# untitled.net
KiCad netlist of a schematic drawn in EAGLE
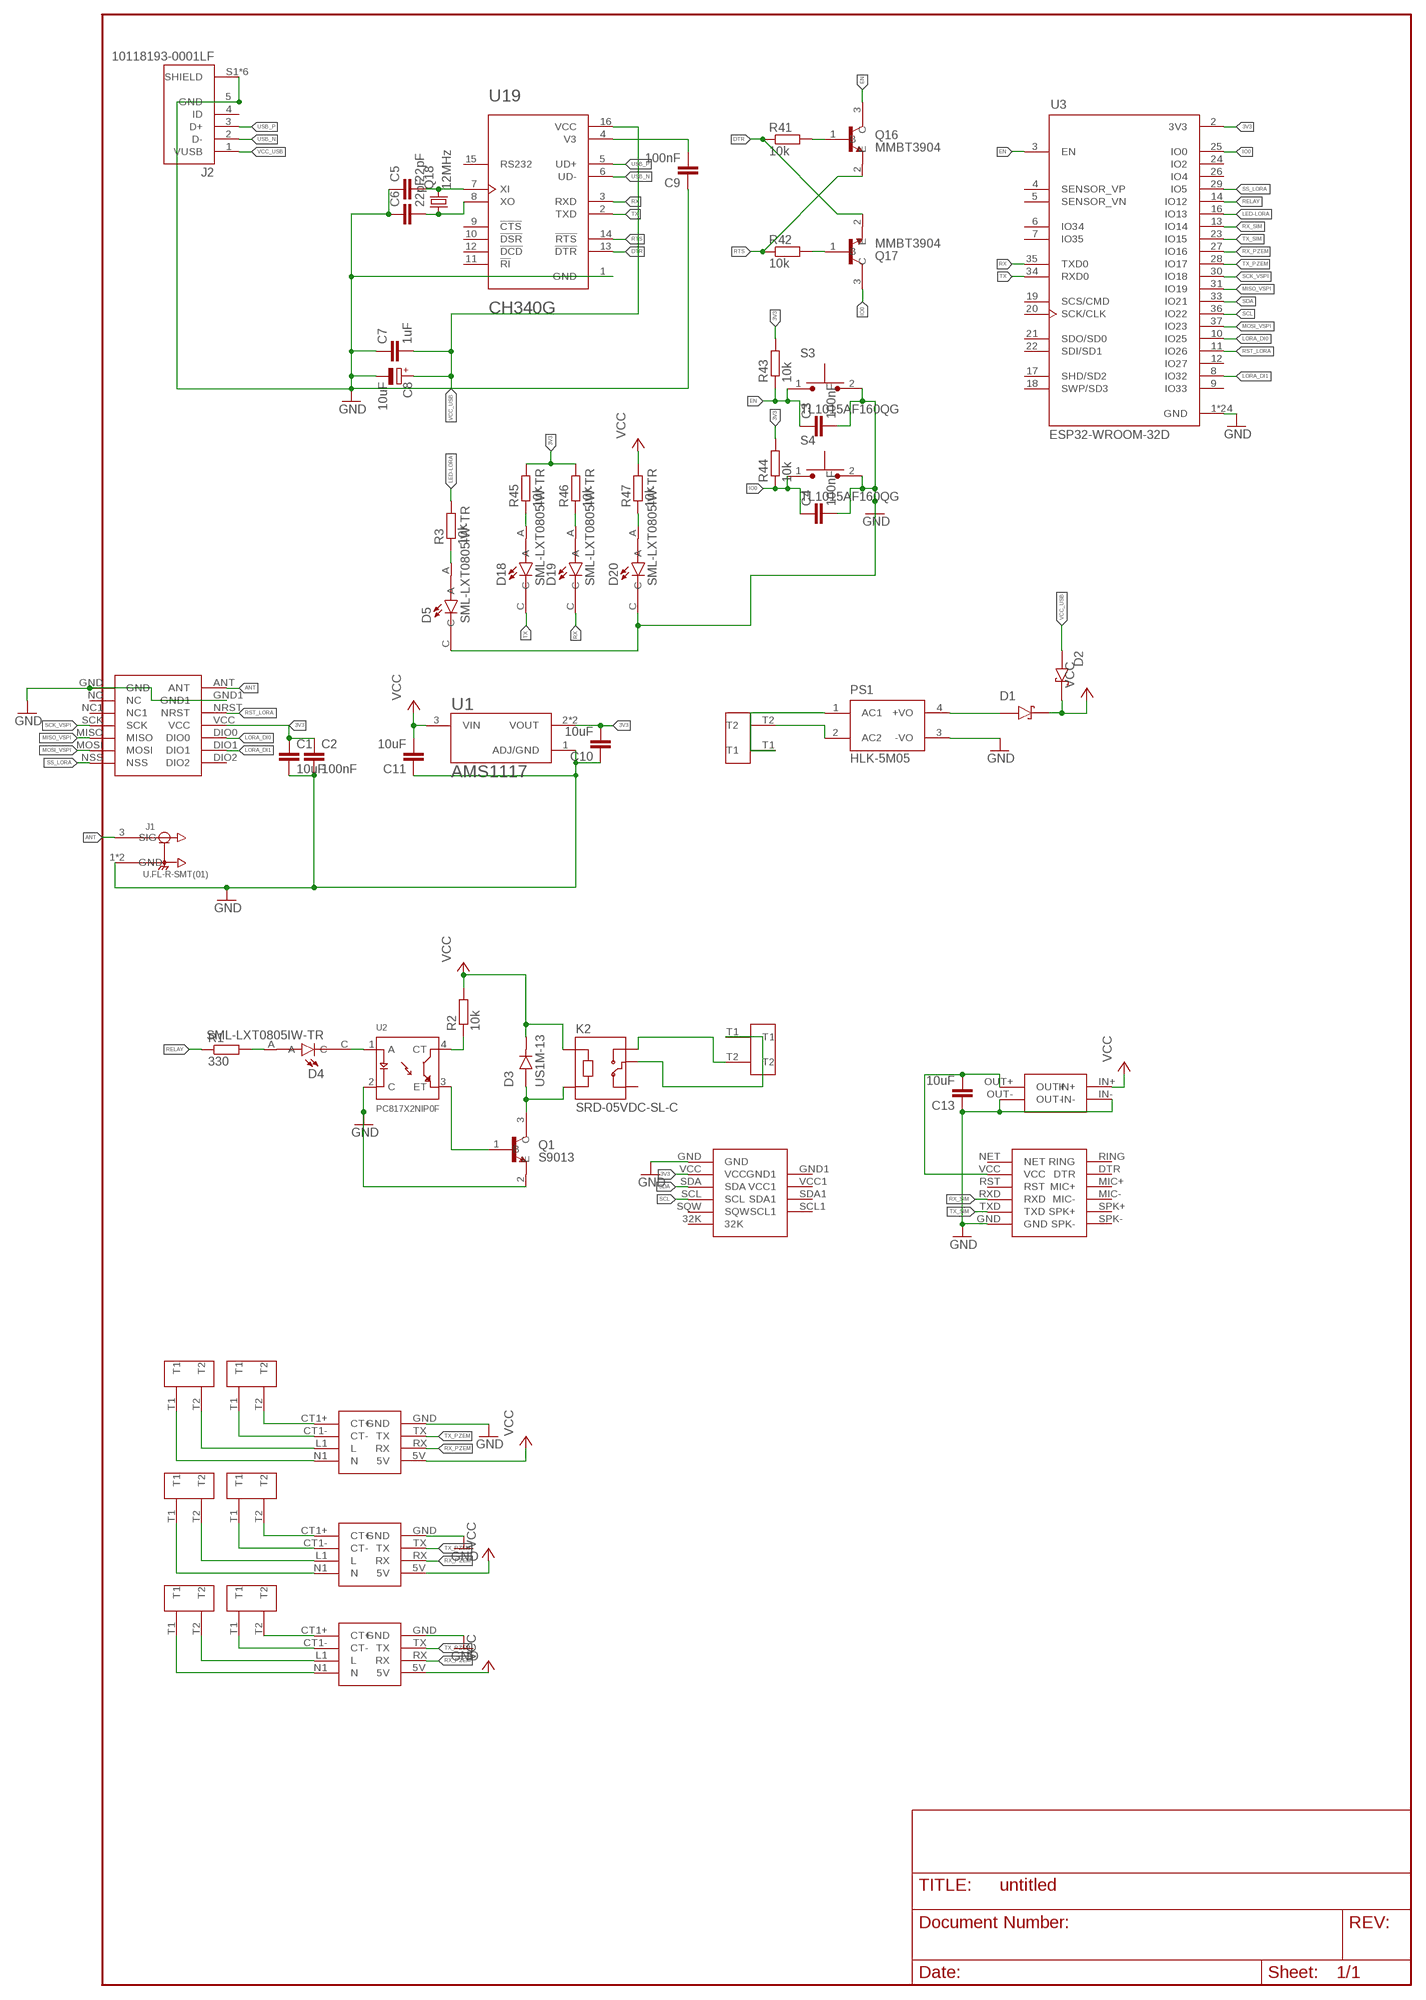
[diagram p0: schematic, sheet 1]

(export (version "E")
  (design (tool "Eeschema 10.0.6"))
  (components
    (comp (ref "C1")
      (value "10uF")
      (footprint "eagle-import:C0805K")
      (libsource (lib "eagle-import") (part "C-EUC0805K"))
    )
    (comp (ref "C2")
      (value "100nF")
      (footprint "eagle-import:C0805K")
      (libsource (lib "eagle-import") (part "C-EUC0805K"))
    )
    (comp (ref "C3")
      (value "100nF")
      (footprint "eagle-import:C0805K")
      (libsource (lib "eagle-import") (part "C-EUC0805K"))
    )
    (comp (ref "C4")
      (value "100nF")
      (footprint "eagle-import:C0805K")
      (libsource (lib "eagle-import") (part "C-EUC0805K"))
    )
    (comp (ref "C5")
      (value "22pF")
      (footprint "eagle-import:C0805K")
      (libsource (lib "eagle-import") (part "C-EUC0805K"))
    )
    (comp (ref "C6")
      (value "22pF")
      (footprint "eagle-import:C0805K")
      (libsource (lib "eagle-import") (part "C-EUC0805K"))
    )
    (comp (ref "C7")
      (value "1uF")
      (footprint "eagle-import:C0805K")
      (libsource (lib "eagle-import") (part "C-EUC0805K"))
    )
    (comp (ref "C8")
      (value "10uF")
      (footprint "eagle-import:153CLV-0505")
      (libsource (lib "eagle-import") (part "CPOL-EU153CLV-0505"))
    )
    (comp (ref "C9")
      (value "100nF")
      (footprint "eagle-import:C0805K")
      (libsource (lib "eagle-import") (part "C-EUC0805K"))
    )
    (comp (ref "C10")
      (value "10uF")
      (footprint "eagle-import:C0805K")
      (libsource (lib "eagle-import") (part "C-EUC0805K"))
    )
    (comp (ref "C11")
      (value "10uF")
      (footprint "eagle-import:C0805K")
      (libsource (lib "eagle-import") (part "C-EUC0805K"))
    )
    (comp (ref "C13")
      (value "10uF")
      (footprint "eagle-import:C0805K")
      (libsource (lib "eagle-import") (part "C-EUC0805K"))
    )
    (comp (ref "D1")
      (value "1N5819HW-7")
      (footprint "eagle-import:SOD3715X145N")
      (fields (field (name "MF") "Diodes Inc."))
      (libsource (lib "eagle-import") (part "1N5819HW-7"))
    )
    (comp (ref "D2")
      (value "1N5819HW-7")
      (footprint "eagle-import:SOD3715X145N")
      (fields (field (name "MF") "Diodes Inc."))
      (libsource (lib "eagle-import") (part "1N5819HW-7"))
    )
    (comp (ref "D3")
      (value "US1M-13")
      (footprint "eagle-import:DIOM5226X240N")
      (fields (field (name "MF") "Diodes Incorporated"))
      (libsource (lib "eagle-import") (part "US1M-13"))
    )
    (comp (ref "D4")
      (value "SML-LXT0805IW-TR")
      (footprint "eagle-import:LEDC2012X120N")
      (fields (field (name "MF") "Lumex Opto/Components"))
      (libsource (lib "eagle-import") (part "SML-LXT0805IW-TR"))
    )
    (comp (ref "D5")
      (value "SML-LXT0805IW-TR")
      (footprint "eagle-import:LEDC2012X120N")
      (fields (field (name "MF") "Lumex Opto/Components"))
      (libsource (lib "eagle-import") (part "SML-LXT0805IW-TR"))
    )
    (comp (ref "D18")
      (value "SML-LXT0805IW-TR")
      (footprint "eagle-import:LEDC2012X120N")
      (fields (field (name "MF") "Lumex Opto/Components"))
      (libsource (lib "eagle-import") (part "SML-LXT0805IW-TR"))
    )
    (comp (ref "D19")
      (value "SML-LXT0805IW-TR")
      (footprint "eagle-import:LEDC2012X120N")
      (fields (field (name "MF") "Lumex Opto/Components"))
      (libsource (lib "eagle-import") (part "SML-LXT0805IW-TR"))
    )
    (comp (ref "D20")
      (value "SML-LXT0805IW-TR")
      (footprint "eagle-import:LEDC2012X120N")
      (fields (field (name "MF") "Lumex Opto/Components"))
      (libsource (lib "eagle-import") (part "SML-LXT0805IW-TR"))
    )
    (comp (ref "J1")
      (value "U.FL-R-SMT(01)")
      (footprint "eagle-import:HRS_U.FL-R-SMT(01)")
      (fields (field (name "MF") "Hirose"))
      (libsource (lib "eagle-import") (part "U.FL-R-SMT(01)"))
    )
    (comp (ref "J2")
      (value "10118193-0001LF")
      (footprint "eagle-import:FCI_10118193-0001LF")
      (fields (field (name "MF") "FCI"))
      (libsource (lib "eagle-import") (part "10118193-0001LF"))
    )
    (comp (ref "K2")
      (value "SRD-05VDC-SL-C")
      (footprint "eagle-import:RELAY_SRD-05VDC-SL-C")
      (fields (field (name "MF") "Songle Relay"))
      (libsource (lib "eagle-import") (part "SRD-05VDC-SL-C"))
    )
    (comp (ref "LORA-NICERF-V1")
      (value "LORA-NICERF-V2")
      (footprint "eagle-import:LORA-NICERF-V2")
      (libsource (lib "eagle-import") (part "LORA-NICERF-V2"))
    )
    (comp (ref "MINI1")
      (value "MINI360")
      (footprint "eagle-import:MINI360")
      (libsource (lib "eagle-import") (part "MINI360"))
    )
    (comp (ref "PS1")
      (value "HLK-5M05")
      (footprint "eagle-import:CONV_HLK-5M05")
      (fields (field (name "MF") "Hi-link"))
      (libsource (lib "eagle-import") (part "HLK-5M05"))
    )
    (comp (ref "PZEM004T1")
      (value "PZEM004T")
      (footprint "eagle-import:PZEM004T")
      (libsource (lib "eagle-import") (part "PZEM004T"))
    )
    (comp (ref "PZEM004T2")
      (value "PZEM004T")
      (footprint "eagle-import:PZEM004T")
      (libsource (lib "eagle-import") (part "PZEM004T"))
    )
    (comp (ref "PZEM004T3")
      (value "PZEM004T")
      (footprint "eagle-import:PZEM004T")
      (libsource (lib "eagle-import") (part "PZEM004T"))
    )
    (comp (ref "Q1")
      (value "S9013")
      (footprint "eagle-import:SOT95P240X120-3N")
      (fields (field (name "MF") "JCET"))
      (libsource (lib "eagle-import") (part "S9013"))
    )
    (comp (ref "Q16")
      (value "MMBT3904")
      (footprint "eagle-import:SOT95P240X120-3N")
      (fields (field (name "MF") "ON Semiconductor"))
      (libsource (lib "eagle-import") (part "MMBT3904"))
    )
    (comp (ref "Q17")
      (value "MMBT3904")
      (footprint "eagle-import:SOT95P240X120-3N")
      (fields (field (name "MF") "ON Semiconductor"))
      (libsource (lib "eagle-import") (part "MMBT3904"))
    )
    (comp (ref "Q18")
      (value "12MHz")
      (footprint "eagle-import:SM49")
      (libsource (lib "eagle-import") (part "CRYSTALSM49"))
    )
    (comp (ref "R1")
      (value "330")
      (footprint "eagle-import:R0805")
      (libsource (lib "eagle-import") (part "R-EU_R0805"))
    )
    (comp (ref "R2")
      (value "10k")
      (footprint "eagle-import:R0805")
      (libsource (lib "eagle-import") (part "R-EU_R0805"))
    )
    (comp (ref "R3")
      (value "10k")
      (footprint "eagle-import:R0805")
      (libsource (lib "eagle-import") (part "R-EU_R0805"))
    )
    (comp (ref "R41")
      (value "10k")
      (footprint "eagle-import:R0805")
      (libsource (lib "eagle-import") (part "R-EU_R0805"))
    )
    (comp (ref "R42")
      (value "10k")
      (footprint "eagle-import:R0805")
      (libsource (lib "eagle-import") (part "R-EU_R0805"))
    )
    (comp (ref "R43")
      (value "10k")
      (footprint "eagle-import:R0805")
      (libsource (lib "eagle-import") (part "R-EU_R0805"))
    )
    (comp (ref "R44")
      (value "10k")
      (footprint "eagle-import:R0805")
      (libsource (lib "eagle-import") (part "R-EU_R0805"))
    )
    (comp (ref "R45")
      (value "10k")
      (footprint "eagle-import:R0805")
      (libsource (lib "eagle-import") (part "R-EU_R0805"))
    )
    (comp (ref "R46")
      (value "10k")
      (footprint "eagle-import:R0805")
      (libsource (lib "eagle-import") (part "R-EU_R0805"))
    )
    (comp (ref "R47")
      (value "10k")
      (footprint "eagle-import:R0805")
      (libsource (lib "eagle-import") (part "R-EU_R0805"))
    )
    (comp (ref "RTC1")
      (value "RTC3231")
      (footprint "eagle-import:RTC3231")
      (libsource (lib "eagle-import") (part "RTC3231"))
    )
    (comp (ref "S3")
      (value "TL1015AF160QG")
      (footprint "eagle-import:SW_TL1015AF160QG")
      (fields (field (name "MF") "E-Switch"))
      (libsource (lib "eagle-import") (part "TL1015AF160QG"))
    )
    (comp (ref "S4")
      (value "TL1015AF160QG")
      (footprint "eagle-import:SW_TL1015AF160QG")
      (fields (field (name "MF") "E-Switch"))
      (libsource (lib "eagle-import") (part "TL1015AF160QG"))
    )
    (comp (ref "SIM800L1")
      (value "SIM800L")
      (footprint "eagle-import:SIM800L")
      (libsource (lib "eagle-import") (part "SIM800L"))
    )
    (comp (ref "TB7.1")
      (value "TB7.62")
      (footprint "eagle-import:TB7.62")
      (libsource (lib "eagle-import") (part "TB7.62"))
    )
    (comp (ref "TB7.2")
      (value "TB7.62")
      (footprint "eagle-import:TB7.62")
      (libsource (lib "eagle-import") (part "TB7.62"))
    )
    (comp (ref "TB7.3")
      (value "TB7.62")
      (footprint "eagle-import:TB7.62")
      (libsource (lib "eagle-import") (part "TB7.62"))
    )
    (comp (ref "TB7.4")
      (value "TB7.62")
      (footprint "eagle-import:TB7.62")
      (libsource (lib "eagle-import") (part "TB7.62"))
    )
    (comp (ref "TB7.5")
      (value "TB7.62")
      (footprint "eagle-import:TB7.62")
      (libsource (lib "eagle-import") (part "TB7.62"))
    )
    (comp (ref "TB7.6")
      (value "TB7.62")
      (footprint "eagle-import:TB7.62")
      (libsource (lib "eagle-import") (part "TB7.62"))
    )
    (comp (ref "TB7.7")
      (value "TB7.62")
      (footprint "eagle-import:TB7.62")
      (libsource (lib "eagle-import") (part "TB7.62"))
    )
    (comp (ref "TB7.8")
      (value "TB7.62")
      (footprint "eagle-import:TB7.62")
      (libsource (lib "eagle-import") (part "TB7.62"))
    )
    (comp (ref "U1")
      (value "AMS1117")
      (footprint "eagle-import:SOT229P700X180-4N")
      (fields (field (name "MF") "Advanced Monolithic Systems"))
      (libsource (lib "eagle-import") (part "AMS1117"))
    )
    (comp (ref "U2")
      (value "PC817X2NIP0F")
      (footprint "eagle-import:SOT254P975X400-4N")
      (fields (field (name "MF") "Sharp Microelectronics"))
      (libsource (lib "eagle-import") (part "PC817X2NIP0F"))
    )
    (comp (ref "U3")
      (value "ESP32-WROOM-32D")
      (footprint "eagle-import:MODULE_ESP32-WROOM-32D")
      (fields (field (name "MF") "Espressif Systems"))
      (libsource (lib "eagle-import") (part "ESP32-WROOM-32D"))
    )
    (comp (ref "U19")
      (value "CH340G")
      (footprint "eagle-import:SOIC127P600X180-16N")
      (fields (field (name "MF") "WCH") (field (name "MP") "Ch340G"))
      (libsource (lib "eagle-import") (part "CH340G"))
    )
  )
  (nets
    (net (code "1") (name "3V3") (class "Default")
      (node (ref "C1") (pin "1") (pinfunction "1_1") (pintype "passive"))
      (node (ref "C10") (pin "2") (pinfunction "2_2") (pintype "passive"))
      (node (ref "C2") (pin "1") (pinfunction "1_1") (pintype "passive"))
      (node (ref "LORA-NICERF-V1") (pin "VCC") (pinfunction "VCC_VCC") (pintype "bidirectional"))
      (node (ref "R43") (pin "2") (pinfunction "2_2") (pintype "passive"))
      (node (ref "R44") (pin "2") (pinfunction "2_2") (pintype "passive"))
      (node (ref "R45") (pin "2") (pinfunction "2_2") (pintype "passive"))
      (node (ref "R46") (pin "2") (pinfunction "2_2") (pintype "passive"))
      (node (ref "RTC1") (pin "VCC") (pinfunction "VCC_VCC") (pintype "bidirectional"))
      (node (ref "U1") (pin "2") (pinfunction "VOUT_2") (pintype "output"))
      (node (ref "U1") (pin "4") (pinfunction "VOUT_4") (pintype "output"))
      (node (ref "U3") (pin "2") (pinfunction "3V3_2") (pintype "power_in"))
    )
    (net (code "2") (name "ANT") (class "Default")
      (node (ref "J1") (pin "3") (pinfunction "SIG_3") (pintype "passive"))
      (node (ref "LORA-NICERF-V1") (pin "ANT") (pinfunction "ANT_ANT") (pintype "bidirectional"))
    )
    (net (code "3") (name "DTR") (class "Default")
      (node (ref "Q17") (pin "2") (pinfunction "E_2") (pintype "passive"))
      (node (ref "R41") (pin "1") (pinfunction "1_1") (pintype "passive"))
      (node (ref "U19") (pin "13") (pinfunction "~{DTR}_13") (pintype "output"))
    )
    (net (code "4") (name "EN") (class "Default")
      (node (ref "C3") (pin "1") (pinfunction "1_1") (pintype "passive"))
      (node (ref "Q16") (pin "3") (pinfunction "C_3") (pintype "passive"))
      (node (ref "R43") (pin "1") (pinfunction "1_1") (pintype "passive"))
      (node (ref "S3") (pin "1") (pinfunction "1_1") (pintype "passive"))
      (node (ref "U3") (pin "3") (pinfunction "EN_3") (pintype "input"))
    )
    (net (code "5") (name "GND") (class "Default")
      (node (ref "C1") (pin "2") (pinfunction "2_2") (pintype "passive"))
      (node (ref "C10") (pin "1") (pinfunction "1_1") (pintype "passive"))
      (node (ref "C11") (pin "1") (pinfunction "1_1") (pintype "passive"))
      (node (ref "C13") (pin "1") (pinfunction "1_1") (pintype "passive"))
      (node (ref "C2") (pin "2") (pinfunction "2_2") (pintype "passive"))
      (node (ref "C3") (pin "2") (pinfunction "2_2") (pintype "passive"))
      (node (ref "C4") (pin "2") (pinfunction "2_2") (pintype "passive"))
      (node (ref "C5") (pin "1") (pinfunction "1_1") (pintype "passive"))
      (node (ref "C6") (pin "1") (pinfunction "1_1") (pintype "passive"))
      (node (ref "C7") (pin "1") (pinfunction "1_1") (pintype "passive"))
      (node (ref "C8") (pin "-") (pinfunction "-_-") (pintype "passive"))
      (node (ref "C9") (pin "1") (pinfunction "1_1") (pintype "passive"))
      (node (ref "D20") (pin "C") (pinfunction "C_C") (pintype "passive"))
      (node (ref "D5") (pin "C") (pinfunction "C_C") (pintype "passive"))
      (node (ref "J1") (pin "1") (pinfunction "GND_1") (pintype "passive"))
      (node (ref "J1") (pin "2") (pinfunction "GND_2") (pintype "passive"))
      (node (ref "J2") (pin "5") (pinfunction "GND_5") (pintype "passive"))
      (node (ref "J2") (pin "S1") (pinfunction "SHIELD_S1") (pintype "passive"))
      (node (ref "J2") (pin "S2") (pinfunction "SHIELD_S2") (pintype "passive"))
      (node (ref "J2") (pin "S3") (pinfunction "SHIELD_S3") (pintype "passive"))
      (node (ref "J2") (pin "S4") (pinfunction "SHIELD_S4") (pintype "passive"))
      (node (ref "J2") (pin "S5") (pinfunction "SHIELD_S5") (pintype "passive"))
      (node (ref "J2") (pin "S6") (pinfunction "SHIELD_S6") (pintype "passive"))
      (node (ref "LORA-NICERF-V1") (pin "GND") (pinfunction "GND_GND") (pintype "bidirectional"))
      (node (ref "LORA-NICERF-V1") (pin "GND1") (pinfunction "GND1_GND1") (pintype "bidirectional"))
      (node (ref "MINI1") (pin "IN-") (pinfunction "IN-_IN-") (pintype "bidirectional"))
      (node (ref "MINI1") (pin "OUT-") (pinfunction "OUT-_OUT-") (pintype "bidirectional"))
      (node (ref "PS1") (pin "3") (pinfunction "-VO_3") (pintype "output"))
      (node (ref "PZEM004T1") (pin "GND") (pinfunction "GND_GND") (pintype "bidirectional"))
      (node (ref "PZEM004T2") (pin "GND") (pinfunction "GND_GND") (pintype "bidirectional"))
      (node (ref "PZEM004T3") (pin "GND") (pinfunction "GND_GND") (pintype "bidirectional"))
      (node (ref "Q1") (pin "2") (pinfunction "E_2") (pintype "passive"))
      (node (ref "RTC1") (pin "GND") (pinfunction "GND_GND") (pintype "bidirectional"))
      (node (ref "S3") (pin "2") (pinfunction "2_2") (pintype "passive"))
      (node (ref "S4") (pin "2") (pinfunction "2_2") (pintype "passive"))
      (node (ref "SIM800L1") (pin "GND") (pinfunction "GND_GND") (pintype "bidirectional"))
      (node (ref "U1") (pin "1") (pinfunction "ADJ/GND_1") (pintype "power_in"))
      (node (ref "U19") (pin "1") (pinfunction "GND_1") (pintype "power_in"))
      (node (ref "U2") (pin "2") (pinfunction "C_2") (pintype "passive"))
      (node (ref "U3") (pin "1") (pinfunction "GND_1") (pintype "power_in"))
      (node (ref "U3") (pin "15") (pinfunction "GND_15") (pintype "power_in"))
      (node (ref "U3") (pin "38") (pinfunction "GND_38") (pintype "power_in"))
      (node (ref "U3") (pin "39_1") (pinfunction "GND_39_1") (pintype "power_in"))
      (node (ref "U3") (pin "39_10") (pinfunction "GND_39_10") (pintype "power_in"))
      (node (ref "U3") (pin "39_11") (pinfunction "GND_39_11") (pintype "power_in"))
      (node (ref "U3") (pin "39_12") (pinfunction "GND_39_12") (pintype "power_in"))
      (node (ref "U3") (pin "39_13") (pinfunction "GND_39_13") (pintype "power_in"))
      (node (ref "U3") (pin "39_14") (pinfunction "GND_39_14") (pintype "power_in"))
      (node (ref "U3") (pin "39_15") (pinfunction "GND_39_15") (pintype "power_in"))
      (node (ref "U3") (pin "39_16") (pinfunction "GND_39_16") (pintype "power_in"))
      (node (ref "U3") (pin "39_17") (pinfunction "GND_39_17") (pintype "power_in"))
      (node (ref "U3") (pin "39_18") (pinfunction "GND_39_18") (pintype "power_in"))
      (node (ref "U3") (pin "39_19") (pinfunction "GND_39_19") (pintype "power_in"))
      (node (ref "U3") (pin "39_2") (pinfunction "GND_39_2") (pintype "power_in"))
      (node (ref "U3") (pin "39_20") (pinfunction "GND_39_20") (pintype "power_in"))
      (node (ref "U3") (pin "39_21") (pinfunction "GND_39_21") (pintype "power_in"))
      (node (ref "U3") (pin "39_3") (pinfunction "GND_39_3") (pintype "power_in"))
      (node (ref "U3") (pin "39_4") (pinfunction "GND_39_4") (pintype "power_in"))
      (node (ref "U3") (pin "39_5") (pinfunction "GND_39_5") (pintype "power_in"))
      (node (ref "U3") (pin "39_6") (pinfunction "GND_39_6") (pintype "power_in"))
      (node (ref "U3") (pin "39_7") (pinfunction "GND_39_7") (pintype "power_in"))
      (node (ref "U3") (pin "39_8") (pinfunction "GND_39_8") (pintype "power_in"))
      (node (ref "U3") (pin "39_9") (pinfunction "GND_39_9") (pintype "power_in"))
    )
    (net (code "6") (name "IO0") (class "Default")
      (node (ref "C4") (pin "1") (pinfunction "1_1") (pintype "passive"))
      (node (ref "Q17") (pin "3") (pinfunction "C_3") (pintype "passive"))
      (node (ref "R44") (pin "1") (pinfunction "1_1") (pintype "passive"))
      (node (ref "S4") (pin "1") (pinfunction "1_1") (pintype "passive"))
      (node (ref "U3") (pin "25") (pinfunction "IO0_25") (pintype "bidirectional"))
    )
    (net (code "7") (name "LED-LORA") (class "Default")
      (node (ref "R3") (pin "2") (pinfunction "2_2") (pintype "passive"))
      (node (ref "U3") (pin "16") (pinfunction "IO13_16") (pintype "bidirectional"))
    )
    (net (code "8") (name "LORA_DI0") (class "Default")
      (node (ref "LORA-NICERF-V1") (pin "DIO0") (pinfunction "DIO0_DIO0") (pintype "bidirectional"))
      (node (ref "U3") (pin "10") (pinfunction "IO25_10") (pintype "bidirectional"))
    )
    (net (code "9") (name "LORA_DI1") (class "Default")
      (node (ref "LORA-NICERF-V1") (pin "DIO1") (pinfunction "DIO1_DIO1") (pintype "bidirectional"))
      (node (ref "U3") (pin "8") (pinfunction "IO32_8") (pintype "bidirectional"))
    )
    (net (code "10") (name "MISO_VSPI") (class "Default")
      (node (ref "LORA-NICERF-V1") (pin "MISO") (pinfunction "MISO_MISO") (pintype "bidirectional"))
      (node (ref "U3") (pin "31") (pinfunction "IO19_31") (pintype "bidirectional"))
    )
    (net (code "11") (name "MOSI_VSPI") (class "Default")
      (node (ref "LORA-NICERF-V1") (pin "MOSI") (pinfunction "MOSI_MOSI") (pintype "bidirectional"))
      (node (ref "U3") (pin "37") (pinfunction "IO23_37") (pintype "bidirectional"))
    )
    (net (code "12") (name "Net-(C13-Pad2)") (class "Default")
      (node (ref "C13") (pin "2") (pinfunction "2_2") (pintype "passive"))
      (node (ref "MINI1") (pin "OUT+") (pinfunction "OUT+_OUT+") (pintype "bidirectional"))
      (node (ref "SIM800L1") (pin "VCC") (pinfunction "VCC_VCC") (pintype "bidirectional"))
    )
    (net (code "13") (name "Net-(D4-PadA)") (class "Default")
      (node (ref "D4") (pin "A") (pinfunction "A_A") (pintype "passive"))
      (node (ref "R1") (pin "2") (pinfunction "2_2") (pintype "passive"))
    )
    (net (code "14") (name "Net-(D5-PadA)") (class "Default")
      (node (ref "D5") (pin "A") (pinfunction "A_A") (pintype "passive"))
      (node (ref "R3") (pin "1") (pinfunction "1_1") (pintype "passive"))
    )
    (net (code "15") (name "Net-(D18-PadA)") (class "Default")
      (node (ref "D18") (pin "A") (pinfunction "A_A") (pintype "passive"))
      (node (ref "R45") (pin "1") (pinfunction "1_1") (pintype "passive"))
    )
    (net (code "16") (name "Net-(D19-PadA)") (class "Default")
      (node (ref "D19") (pin "A") (pinfunction "A_A") (pintype "passive"))
      (node (ref "R46") (pin "1") (pinfunction "1_1") (pintype "passive"))
    )
    (net (code "17") (name "Net-(D20-PadA)") (class "Default")
      (node (ref "D20") (pin "A") (pinfunction "A_A") (pintype "passive"))
      (node (ref "R47") (pin "1") (pinfunction "1_1") (pintype "passive"))
    )
    (net (code "18") (name "Net-(K2-PadCOM)") (class "Default")
      (node (ref "K2") (pin "COM") (pinfunction "COM_COM") (pintype "passive"))
      (node (ref "TB7.2") (pin "T1") (pinfunction "T1_T1") (pintype "bidirectional"))
    )
    (net (code "19") (name "Net-(K2-PadNO)") (class "Default")
      (node (ref "K2") (pin "NO") (pinfunction "NO_NO") (pintype "passive"))
      (node (ref "TB7.2") (pin "T2") (pinfunction "T2_T2") (pintype "bidirectional"))
    )
    (net (code "20") (name "Net-(PS1-+VO)") (class "Default")
      (node (ref "D1") (pin "A") (pinfunction "A_A") (pintype "passive"))
      (node (ref "PS1") (pin "4") (pinfunction "+VO_4") (pintype "output"))
    )
    (net (code "21") (name "Net-(PS1-AC1)") (class "Default")
      (node (ref "PS1") (pin "1") (pinfunction "AC1_1") (pintype "input"))
      (node (ref "TB7.1") (pin "T1") (pinfunction "T1_T1") (pintype "bidirectional"))
    )
    (net (code "22") (name "Net-(PS1-AC2)") (class "Default")
      (node (ref "PS1") (pin "2") (pinfunction "AC2_2") (pintype "input"))
      (node (ref "TB7.1") (pin "T2") (pinfunction "T2_T2") (pintype "bidirectional"))
    )
    (net (code "23") (name "Net-(PZEM004T1-CT+)") (class "Default")
      (node (ref "PZEM004T1") (pin "CT1+") (pinfunction "CT+_CT1+") (pintype "bidirectional"))
      (node (ref "TB7.3") (pin "T2") (pinfunction "T2_T2") (pintype "bidirectional"))
    )
    (net (code "24") (name "Net-(PZEM004T1-CT-)") (class "Default")
      (node (ref "PZEM004T1") (pin "CT1-") (pinfunction "CT-_CT1-") (pintype "bidirectional"))
      (node (ref "TB7.3") (pin "T1") (pinfunction "T1_T1") (pintype "bidirectional"))
    )
    (net (code "25") (name "Net-(PZEM004T1-L)") (class "Default")
      (node (ref "PZEM004T1") (pin "L1") (pinfunction "L_L1") (pintype "bidirectional"))
      (node (ref "TB7.4") (pin "T2") (pinfunction "T2_T2") (pintype "bidirectional"))
    )
    (net (code "26") (name "Net-(PZEM004T1-N)") (class "Default")
      (node (ref "PZEM004T1") (pin "N1") (pinfunction "N_N1") (pintype "bidirectional"))
      (node (ref "TB7.4") (pin "T1") (pinfunction "T1_T1") (pintype "bidirectional"))
    )
    (net (code "27") (name "Net-(PZEM004T2-CT+)") (class "Default")
      (node (ref "PZEM004T2") (pin "CT1+") (pinfunction "CT+_CT1+") (pintype "bidirectional"))
      (node (ref "TB7.5") (pin "T2") (pinfunction "T2_T2") (pintype "bidirectional"))
    )
    (net (code "28") (name "Net-(PZEM004T2-CT-)") (class "Default")
      (node (ref "PZEM004T2") (pin "CT1-") (pinfunction "CT-_CT1-") (pintype "bidirectional"))
      (node (ref "TB7.5") (pin "T1") (pinfunction "T1_T1") (pintype "bidirectional"))
    )
    (net (code "29") (name "Net-(PZEM004T2-L)") (class "Default")
      (node (ref "PZEM004T2") (pin "L1") (pinfunction "L_L1") (pintype "bidirectional"))
      (node (ref "TB7.6") (pin "T2") (pinfunction "T2_T2") (pintype "bidirectional"))
    )
    (net (code "30") (name "Net-(PZEM004T2-N)") (class "Default")
      (node (ref "PZEM004T2") (pin "N1") (pinfunction "N_N1") (pintype "bidirectional"))
      (node (ref "TB7.6") (pin "T1") (pinfunction "T1_T1") (pintype "bidirectional"))
    )
    (net (code "31") (name "Net-(PZEM004T3-CT+)") (class "Default")
      (node (ref "PZEM004T3") (pin "CT1+") (pinfunction "CT+_CT1+") (pintype "bidirectional"))
      (node (ref "TB7.7") (pin "T2") (pinfunction "T2_T2") (pintype "bidirectional"))
    )
    (net (code "32") (name "Net-(PZEM004T3-CT-)") (class "Default")
      (node (ref "PZEM004T3") (pin "CT1-") (pinfunction "CT-_CT1-") (pintype "bidirectional"))
      (node (ref "TB7.7") (pin "T1") (pinfunction "T1_T1") (pintype "bidirectional"))
    )
    (net (code "33") (name "Net-(PZEM004T3-L)") (class "Default")
      (node (ref "PZEM004T3") (pin "L1") (pinfunction "L_L1") (pintype "bidirectional"))
      (node (ref "TB7.8") (pin "T2") (pinfunction "T2_T2") (pintype "bidirectional"))
    )
    (net (code "34") (name "Net-(PZEM004T3-N)") (class "Default")
      (node (ref "PZEM004T3") (pin "N1") (pinfunction "N_N1") (pintype "bidirectional"))
      (node (ref "TB7.8") (pin "T1") (pinfunction "T1_T1") (pintype "bidirectional"))
    )
    (net (code "35") (name "Net-(Q1-B)") (class "Default")
      (node (ref "Q1") (pin "1") (pinfunction "B_1") (pintype "passive"))
      (node (ref "U2") (pin "3") (pinfunction "ET_3") (pintype "passive"))
    )
    (net (code "36") (name "Net-(Q1-C)") (class "Default")
      (node (ref "D3") (pin "A") (pinfunction "A_A") (pintype "passive"))
      (node (ref "K2") (pin "A2") (pinfunction "A2_A2") (pintype "passive"))
      (node (ref "Q1") (pin "3") (pinfunction "C_3") (pintype "passive"))
    )
    (net (code "37") (name "Net-(Q16-B)") (class "Default")
      (node (ref "Q16") (pin "1") (pinfunction "B_1") (pintype "passive"))
      (node (ref "R41") (pin "2") (pinfunction "2_2") (pintype "passive"))
    )
    (net (code "38") (name "Net-(Q17-B)") (class "Default")
      (node (ref "Q17") (pin "1") (pinfunction "B_1") (pintype "passive"))
      (node (ref "R42") (pin "2") (pinfunction "2_2") (pintype "passive"))
    )
    (net (code "39") (name "Net-(U2-A)") (class "Default")
      (node (ref "D4") (pin "C") (pinfunction "C_C") (pintype "passive"))
      (node (ref "U2") (pin "1") (pinfunction "A_1") (pintype "passive"))
    )
    (net (code "40") (name "Net-(U2-CT)") (class "Default")
      (node (ref "R2") (pin "1") (pinfunction "1_1") (pintype "passive"))
      (node (ref "U2") (pin "4") (pinfunction "CT_4") (pintype "passive"))
    )
    (net (code "41") (name "Net-(U19-V3)") (class "Default")
      (node (ref "C9") (pin "2") (pinfunction "2_2") (pintype "passive"))
      (node (ref "U19") (pin "4") (pinfunction "V3_4") (pintype "power_in"))
    )
    (net (code "42") (name "Net-(U19-XI)") (class "Default")
      (node (ref "C5") (pin "2") (pinfunction "2_2") (pintype "passive"))
      (node (ref "Q18") (pin "2") (pinfunction "2_2") (pintype "passive"))
      (node (ref "U19") (pin "7") (pinfunction "XI_7") (pintype "input"))
    )
    (net (code "43") (name "Net-(U19-XO)") (class "Default")
      (node (ref "C6") (pin "2") (pinfunction "2_2") (pintype "passive"))
      (node (ref "Q18") (pin "1") (pinfunction "1_1") (pintype "passive"))
      (node (ref "U19") (pin "8") (pinfunction "XO_8") (pintype "output"))
    )
    (net (code "44") (name "RELAY") (class "Default")
      (node (ref "R1") (pin "1") (pinfunction "1_1") (pintype "passive"))
      (node (ref "U3") (pin "14") (pinfunction "IO12_14") (pintype "bidirectional"))
    )
    (net (code "45") (name "RST_LORA") (class "Default")
      (node (ref "LORA-NICERF-V1") (pin "NRST") (pinfunction "NRST_NRST") (pintype "bidirectional"))
      (node (ref "U3") (pin "11") (pinfunction "IO26_11") (pintype "bidirectional"))
    )
    (net (code "46") (name "RTS") (class "Default")
      (node (ref "Q16") (pin "2") (pinfunction "E_2") (pintype "passive"))
      (node (ref "R42") (pin "1") (pinfunction "1_1") (pintype "passive"))
      (node (ref "U19") (pin "14") (pinfunction "~{RTS}_14") (pintype "output"))
    )
    (net (code "47") (name "RX") (class "Default")
      (node (ref "D19") (pin "C") (pinfunction "C_C") (pintype "passive"))
      (node (ref "U19") (pin "3") (pinfunction "RXD_3") (pintype "input"))
      (node (ref "U3") (pin "35") (pinfunction "TXD0_35") (pintype "bidirectional"))
    )
    (net (code "48") (name "RX_PZEM") (class "Default")
      (node (ref "PZEM004T1") (pin "RX") (pinfunction "RX_RX") (pintype "bidirectional"))
      (node (ref "PZEM004T2") (pin "RX") (pinfunction "RX_RX") (pintype "bidirectional"))
      (node (ref "PZEM004T3") (pin "RX") (pinfunction "RX_RX") (pintype "bidirectional"))
      (node (ref "U3") (pin "27") (pinfunction "IO16_27") (pintype "bidirectional"))
    )
    (net (code "49") (name "RX_SIM") (class "Default")
      (node (ref "SIM800L1") (pin "RXD") (pinfunction "RXD_RXD") (pintype "bidirectional"))
      (node (ref "U3") (pin "13") (pinfunction "IO14_13") (pintype "bidirectional"))
    )
    (net (code "50") (name "SCK_VSPI") (class "Default")
      (node (ref "LORA-NICERF-V1") (pin "SCK") (pinfunction "SCK_SCK") (pintype "bidirectional"))
      (node (ref "U3") (pin "30") (pinfunction "IO18_30") (pintype "bidirectional"))
    )
    (net (code "51") (name "SCL") (class "Default")
      (node (ref "RTC1") (pin "SCL") (pinfunction "SCL_SCL") (pintype "bidirectional"))
      (node (ref "U3") (pin "36") (pinfunction "IO22_36") (pintype "bidirectional"))
    )
    (net (code "52") (name "SDA") (class "Default")
      (node (ref "RTC1") (pin "SDA") (pinfunction "SDA_SDA") (pintype "bidirectional"))
      (node (ref "U3") (pin "33") (pinfunction "IO21_33") (pintype "bidirectional"))
    )
    (net (code "53") (name "SS_LORA") (class "Default")
      (node (ref "LORA-NICERF-V1") (pin "NSS") (pinfunction "NSS_NSS") (pintype "bidirectional"))
      (node (ref "U3") (pin "29") (pinfunction "IO5_29") (pintype "bidirectional"))
    )
    (net (code "54") (name "TX") (class "Default")
      (node (ref "D18") (pin "C") (pinfunction "C_C") (pintype "passive"))
      (node (ref "U19") (pin "2") (pinfunction "TXD_2") (pintype "output"))
      (node (ref "U3") (pin "34") (pinfunction "RXD0_34") (pintype "bidirectional"))
    )
    (net (code "55") (name "TX_PZEM") (class "Default")
      (node (ref "PZEM004T1") (pin "TX") (pinfunction "TX_TX") (pintype "bidirectional"))
      (node (ref "PZEM004T2") (pin "TX") (pinfunction "TX_TX") (pintype "bidirectional"))
      (node (ref "PZEM004T3") (pin "TX") (pinfunction "TX_TX") (pintype "bidirectional"))
      (node (ref "U3") (pin "28") (pinfunction "IO17_28") (pintype "bidirectional"))
    )
    (net (code "56") (name "TX_SIM") (class "Default")
      (node (ref "SIM800L1") (pin "TXD") (pinfunction "TXD_TXD") (pintype "bidirectional"))
      (node (ref "U3") (pin "23") (pinfunction "IO15_23") (pintype "bidirectional"))
    )
    (net (code "57") (name "USB_N") (class "Default")
      (node (ref "J2") (pin "2") (pinfunction "D-_2") (pintype "passive"))
      (node (ref "U19") (pin "6") (pinfunction "UD-_6") (pintype "bidirectional"))
    )
    (net (code "58") (name "USB_P") (class "Default")
      (node (ref "J2") (pin "3") (pinfunction "D+_3") (pintype "passive"))
      (node (ref "U19") (pin "5") (pinfunction "UD+_5") (pintype "bidirectional"))
    )
    (net (code "59") (name "VCC") (class "Default")
      (node (ref "C11") (pin "2") (pinfunction "2_2") (pintype "passive"))
      (node (ref "D1") (pin "C") (pinfunction "K_C") (pintype "passive"))
      (node (ref "D2") (pin "C") (pinfunction "K_C") (pintype "passive"))
      (node (ref "D3") (pin "C") (pinfunction "K_C") (pintype "passive"))
      (node (ref "K2") (pin "A1") (pinfunction "A1_A1") (pintype "passive"))
      (node (ref "MINI1") (pin "IN+") (pinfunction "IN+_IN+") (pintype "bidirectional"))
      (node (ref "PZEM004T1") (pin "5V") (pinfunction "5V_5V") (pintype "bidirectional"))
      (node (ref "PZEM004T2") (pin "5V") (pinfunction "5V_5V") (pintype "bidirectional"))
      (node (ref "PZEM004T3") (pin "5V") (pinfunction "5V_5V") (pintype "bidirectional"))
      (node (ref "R2") (pin "2") (pinfunction "2_2") (pintype "passive"))
      (node (ref "R47") (pin "2") (pinfunction "2_2") (pintype "passive"))
      (node (ref "U1") (pin "3") (pinfunction "VIN_3") (pintype "input"))
    )
    (net (code "60") (name "VCC_USB") (class "Default")
      (node (ref "C7") (pin "2") (pinfunction "2_2") (pintype "passive"))
      (node (ref "C8") (pin "+") (pinfunction "+_+") (pintype "passive"))
      (node (ref "D2") (pin "A") (pinfunction "A_A") (pintype "passive"))
      (node (ref "J2") (pin "1") (pinfunction "VUSB_1") (pintype "passive"))
      (node (ref "U19") (pin "16") (pinfunction "VCC_16") (pintype "power_in"))
    )
    (net (code "61") (name "unconnected-(J2-ID-Pad4)") (class "Default")
      (node (ref "J2") (pin "4") (pinfunction "ID_4") (pintype "passive"))
    )
    (net (code "62") (name "unconnected-(K2-PadNC)") (class "Default")
      (node (ref "K2") (pin "NC") (pinfunction "NC_NC") (pintype "passive"))
    )
    (net (code "63") (name "unconnected-(LORA-NICERF-V1-PadDIO2)") (class "Default")
      (node (ref "LORA-NICERF-V1") (pin "DIO2") (pinfunction "DIO2_DIO2") (pintype "bidirectional"))
    )
    (net (code "64") (name "unconnected-(LORA-NICERF-V1-PadNC)") (class "Default")
      (node (ref "LORA-NICERF-V1") (pin "NC") (pinfunction "NC_NC") (pintype "bidirectional"))
    )
    (net (code "65") (name "unconnected-(LORA-NICERF-V1-PadNC1)") (class "Default")
      (node (ref "LORA-NICERF-V1") (pin "NC1") (pinfunction "NC1_NC1") (pintype "bidirectional"))
    )
    (net (code "66") (name "unconnected-(RTC1-Pad32K)") (class "Default")
      (node (ref "RTC1") (pin "32K") (pinfunction "32K_32K") (pintype "bidirectional"))
    )
    (net (code "67") (name "unconnected-(RTC1-PadGND1)") (class "Default")
      (node (ref "RTC1") (pin "GND1") (pinfunction "GND1_GND1") (pintype "bidirectional"))
    )
    (net (code "68") (name "unconnected-(RTC1-PadSCL1)") (class "Default")
      (node (ref "RTC1") (pin "SCL1") (pinfunction "SCL1_SCL1") (pintype "bidirectional"))
    )
    (net (code "69") (name "unconnected-(RTC1-PadSDA1)") (class "Default")
      (node (ref "RTC1") (pin "SDA1") (pinfunction "SDA1_SDA1") (pintype "bidirectional"))
    )
    (net (code "70") (name "unconnected-(RTC1-PadSQW)") (class "Default")
      (node (ref "RTC1") (pin "SQW") (pinfunction "SQW_SQW") (pintype "bidirectional"))
    )
    (net (code "71") (name "unconnected-(RTC1-PadVCC1)") (class "Default")
      (node (ref "RTC1") (pin "VCC1") (pinfunction "VCC1_VCC1") (pintype "bidirectional"))
    )
    (net (code "72") (name "unconnected-(SIM800L1-PadDTR)") (class "Default")
      (node (ref "SIM800L1") (pin "DTR") (pinfunction "DTR_DTR") (pintype "bidirectional"))
    )
    (net (code "73") (name "unconnected-(SIM800L1-PadMIC+)") (class "Default")
      (node (ref "SIM800L1") (pin "MIC+") (pinfunction "MIC+_MIC+") (pintype "bidirectional"))
    )
    (net (code "74") (name "unconnected-(SIM800L1-PadMIC-)") (class "Default")
      (node (ref "SIM800L1") (pin "MIC-") (pinfunction "MIC-_MIC-") (pintype "bidirectional"))
    )
    (net (code "75") (name "unconnected-(SIM800L1-PadNET)") (class "Default")
      (node (ref "SIM800L1") (pin "NET") (pinfunction "NET_NET") (pintype "bidirectional"))
    )
    (net (code "76") (name "unconnected-(SIM800L1-PadRING)") (class "Default")
      (node (ref "SIM800L1") (pin "RING") (pinfunction "RING_RING") (pintype "bidirectional"))
    )
    (net (code "77") (name "unconnected-(SIM800L1-PadRST)") (class "Default")
      (node (ref "SIM800L1") (pin "RST") (pinfunction "RST_RST") (pintype "bidirectional"))
    )
    (net (code "78") (name "unconnected-(SIM800L1-PadSPK+)") (class "Default")
      (node (ref "SIM800L1") (pin "SPK+") (pinfunction "SPK+_SPK+") (pintype "bidirectional"))
    )
    (net (code "79") (name "unconnected-(SIM800L1-PadSPK-)") (class "Default")
      (node (ref "SIM800L1") (pin "SPK-") (pinfunction "SPK-_SPK-") (pintype "bidirectional"))
    )
    (net (code "80") (name "unconnected-(U3-IO2-Pad24)") (class "Default")
      (node (ref "U3") (pin "24") (pinfunction "IO2_24") (pintype "bidirectional"))
    )
    (net (code "81") (name "unconnected-(U3-IO4-Pad26)") (class "Default")
      (node (ref "U3") (pin "26") (pinfunction "IO4_26") (pintype "bidirectional"))
    )
    (net (code "82") (name "unconnected-(U3-IO27-Pad12)") (class "Default")
      (node (ref "U3") (pin "12") (pinfunction "IO27_12") (pintype "bidirectional"))
    )
    (net (code "83") (name "unconnected-(U3-IO33-Pad9)") (class "Default")
      (node (ref "U3") (pin "9") (pinfunction "IO33_9") (pintype "bidirectional"))
    )
    (net (code "84") (name "unconnected-(U3-IO34-Pad6)") (class "Default")
      (node (ref "U3") (pin "6") (pinfunction "IO34_6") (pintype "input"))
    )
    (net (code "85") (name "unconnected-(U3-IO35-Pad7)") (class "Default")
      (node (ref "U3") (pin "7") (pinfunction "IO35_7") (pintype "input"))
    )
    (net (code "86") (name "unconnected-(U3-SCK{slash}CLK-Pad20)") (class "Default")
      (node (ref "U3") (pin "20") (pinfunction "SCK/CLK_20") (pintype "bidirectional"))
    )
    (net (code "87") (name "unconnected-(U3-SCS{slash}CMD-Pad19)") (class "Default")
      (node (ref "U3") (pin "19") (pinfunction "SCS/CMD_19") (pintype "bidirectional"))
    )
    (net (code "88") (name "unconnected-(U3-SDI{slash}SD1-Pad22)") (class "Default")
      (node (ref "U3") (pin "22") (pinfunction "SDI/SD1_22") (pintype "bidirectional"))
    )
    (net (code "89") (name "unconnected-(U3-SDO{slash}SD0-Pad21)") (class "Default")
      (node (ref "U3") (pin "21") (pinfunction "SDO/SD0_21") (pintype "bidirectional"))
    )
    (net (code "90") (name "unconnected-(U3-SENSOR_VN-Pad5)") (class "Default")
      (node (ref "U3") (pin "5") (pinfunction "SENSOR_VN_5") (pintype "input"))
    )
    (net (code "91") (name "unconnected-(U3-SENSOR_VP-Pad4)") (class "Default")
      (node (ref "U3") (pin "4") (pinfunction "SENSOR_VP_4") (pintype "input"))
    )
    (net (code "92") (name "unconnected-(U3-SHD{slash}SD2-Pad17)") (class "Default")
      (node (ref "U3") (pin "17") (pinfunction "SHD/SD2_17") (pintype "bidirectional"))
    )
    (net (code "93") (name "unconnected-(U3-SWP{slash}SD3-Pad18)") (class "Default")
      (node (ref "U3") (pin "18") (pinfunction "SWP/SD3_18") (pintype "bidirectional"))
    )
    (net (code "94") (name "unconnected-(U19-RS232-Pad15)") (class "Default")
      (node (ref "U19") (pin "15") (pinfunction "RS232_15") (pintype "input"))
    )
    (net (code "95") (name "unconnected-(U19-~{CTS}-Pad9)") (class "Default")
      (node (ref "U19") (pin "9") (pinfunction "~{CTS}_9") (pintype "input"))
    )
    (net (code "96") (name "unconnected-(U19-~{DCD}-Pad12)") (class "Default")
      (node (ref "U19") (pin "12") (pinfunction "~{DCD}_12") (pintype "input"))
    )
    (net (code "97") (name "unconnected-(U19-~{DSR}-Pad10)") (class "Default")
      (node (ref "U19") (pin "10") (pinfunction "~{DSR}_10") (pintype "input"))
    )
    (net (code "98") (name "unconnected-(U19-~{RI}-Pad11)") (class "Default")
      (node (ref "U19") (pin "11") (pinfunction "~{RI}_11") (pintype "input"))
    )
  )
)
